# top_g.net
KiCad netlist of a schematic drawn in Altium Designer
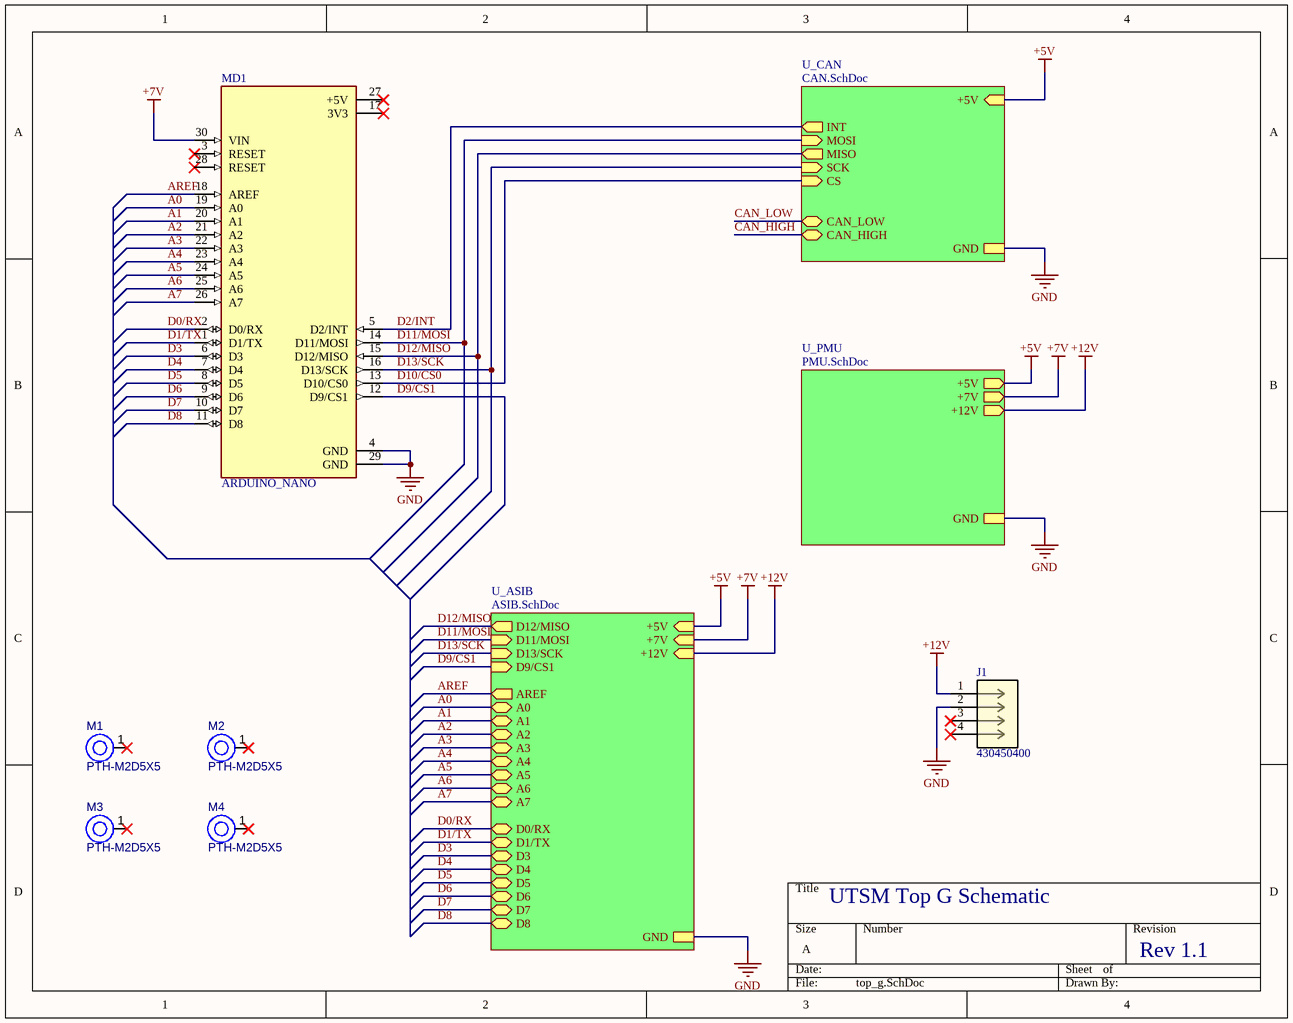
[diagram p0: top_g.SchDoc]

(export (version "E")
  (design (tool "Eeschema 10.0.6"))
  (components
    (comp (ref "J1")
      (value "430450400")
      (footprint "top_g:CON_430450400_MOL")
      (description "+12 from Battery")
      (libsource (lib "top_g") (part "430450400"))
    )
    (comp (ref "M1")
      (value "PTH-M2D5X5")
      (footprint "PTH-M2D5X5")
      (description "M2 PTH (2.5mm), 5mm pad")
      (libsource (lib "top_g") (part "PTH-M2D5X5"))
    )
    (comp (ref "M2")
      (value "PTH-M2D5X5")
      (footprint "PTH-M2D5X5")
      (description "M2 PTH (2.5mm), 5mm pad")
      (libsource (lib "top_g") (part "PTH-M2D5X5"))
    )
    (comp (ref "M3")
      (value "PTH-M2D5X5")
      (footprint "PTH-M2D5X5")
      (description "M2 PTH (2.5mm), 5mm pad")
      (libsource (lib "top_g") (part "PTH-M2D5X5"))
    )
    (comp (ref "M4")
      (value "PTH-M2D5X5")
      (footprint "PTH-M2D5X5")
      (description "M2 PTH (2.5mm), 5mm pad")
      (libsource (lib "top_g") (part "PTH-M2D5X5"))
    )
    (comp (ref "MD1")
      (value "ARDUINO_NANO")
      (footprint "SHIELD_ARDUINO_NANO")
      (description "Small, complete, and breadboard-friendly board based on the ATmega328 (Arduino Nano 3.x)")
      (fields (field (name "MP") "Arduino Nano") (field (name "MF") "Arduino"))
      (libsource (lib "top_g") (part "ARDUINO_NANO"))
    )
  )
  (nets
    (net (code "2") (name "+7V") (class "Default")
      (node (ref "MD1") (pin "30") (pinfunction "VIN_30") (pintype "input"))
    )
    (net (code "3") (name "+12V") (class "Default")
      (node (ref "J1") (pin "1") (pinfunction "1_1") (pintype "passive"))
    )
    (net (code "4") (name "/A0") (class "Default")
      (node (ref "MD1") (pin "19") (pinfunction "A0_19") (pintype "input"))
    )
    (net (code "5") (name "/A1") (class "Default")
      (node (ref "MD1") (pin "20") (pinfunction "A1_20") (pintype "input"))
    )
    (net (code "6") (name "/A2") (class "Default")
      (node (ref "MD1") (pin "21") (pinfunction "A2_21") (pintype "input"))
    )
    (net (code "7") (name "/A3") (class "Default")
      (node (ref "MD1") (pin "22") (pinfunction "A3_22") (pintype "input"))
    )
    (net (code "8") (name "/A4") (class "Default")
      (node (ref "MD1") (pin "23") (pinfunction "A4_23") (pintype "input"))
    )
    (net (code "9") (name "/A5") (class "Default")
      (node (ref "MD1") (pin "24") (pinfunction "A5_24") (pintype "input"))
    )
    (net (code "10") (name "/A6") (class "Default")
      (node (ref "MD1") (pin "25") (pinfunction "A6_25") (pintype "input"))
    )
    (net (code "11") (name "/A7") (class "Default")
      (node (ref "MD1") (pin "26") (pinfunction "A7_26") (pintype "input"))
    )
    (net (code "12") (name "/AREF") (class "Default")
      (node (ref "MD1") (pin "18") (pinfunction "AREF_18") (pintype "input"))
    )
    (net (code "15") (name "/D0{slash}RX") (class "Default")
      (node (ref "MD1") (pin "2") (pinfunction "D0/RX_2") (pintype "bidirectional"))
    )
    (net (code "16") (name "/D1{slash}TX") (class "Default")
      (node (ref "MD1") (pin "1") (pinfunction "D1/TX_1") (pintype "bidirectional"))
    )
    (net (code "17") (name "/D2{slash}INT") (class "Default")
      (node (ref "MD1") (pin "5") (pinfunction "D2/INT_5") (pintype "input"))
    )
    (net (code "18") (name "/D3") (class "Default")
      (node (ref "MD1") (pin "6") (pinfunction "D3_6") (pintype "bidirectional"))
    )
    (net (code "19") (name "/D4") (class "Default")
      (node (ref "MD1") (pin "7") (pinfunction "D4_7") (pintype "bidirectional"))
    )
    (net (code "20") (name "/D5") (class "Default")
      (node (ref "MD1") (pin "8") (pinfunction "D5_8") (pintype "bidirectional"))
    )
    (net (code "21") (name "/D6") (class "Default")
      (node (ref "MD1") (pin "9") (pinfunction "D6_9") (pintype "bidirectional"))
    )
    (net (code "22") (name "/D7") (class "Default")
      (node (ref "MD1") (pin "10") (pinfunction "D7_10") (pintype "bidirectional"))
    )
    (net (code "23") (name "/D8") (class "Default")
      (node (ref "MD1") (pin "11") (pinfunction "D8_11") (pintype "bidirectional"))
    )
    (net (code "24") (name "/D9{slash}CS1") (class "Default")
      (node (ref "MD1") (pin "12") (pinfunction "D9/CS1_12") (pintype "output"))
    )
    (net (code "25") (name "/D10{slash}CS0") (class "Default")
      (node (ref "MD1") (pin "13") (pinfunction "D10/CS0_13") (pintype "output"))
    )
    (net (code "26") (name "/D11{slash}MOSI") (class "Default")
      (node (ref "MD1") (pin "14") (pinfunction "D11/MOSI_14") (pintype "output"))
    )
    (net (code "27") (name "/D12{slash}MISO") (class "Default")
      (node (ref "MD1") (pin "15") (pinfunction "D12/MISO_15") (pintype "input"))
    )
    (net (code "28") (name "/D13{slash}SCK") (class "Default")
      (node (ref "MD1") (pin "16") (pinfunction "D13/SCK_16") (pintype "output"))
    )
    (net (code "29") (name "GND") (class "Default")
      (node (ref "J1") (pin "2") (pinfunction "2_2") (pintype "passive"))
      (node (ref "MD1") (pin "29") (pinfunction "GND_29") (pintype "power_in"))
      (node (ref "MD1") (pin "4") (pinfunction "GND_4") (pintype "power_in"))
    )
    (net (code "30") (name "unconnected-(J1-Pad3)") (class "Default")
      (node (ref "J1") (pin "3") (pinfunction "3_3") (pintype "passive+no_connect"))
    )
    (net (code "31") (name "unconnected-(J1-Pad4)") (class "Default")
      (node (ref "J1") (pin "4") (pinfunction "4_4") (pintype "passive+no_connect"))
    )
    (net (code "32") (name "unconnected-(M1-H1-Pad1)") (class "Default")
      (node (ref "M1") (pin "1") (pinfunction "H1_1") (pintype "passive+no_connect"))
    )
    (net (code "33") (name "unconnected-(M2-H1-Pad1)") (class "Default")
      (node (ref "M2") (pin "1") (pinfunction "H1_1") (pintype "passive+no_connect"))
    )
    (net (code "34") (name "unconnected-(M3-H1-Pad1)") (class "Default")
      (node (ref "M3") (pin "1") (pinfunction "H1_1") (pintype "passive+no_connect"))
    )
    (net (code "35") (name "unconnected-(M4-H1-Pad1)") (class "Default")
      (node (ref "M4") (pin "1") (pinfunction "H1_1") (pintype "passive+no_connect"))
    )
    (net (code "36") (name "unconnected-(MD1-+5V-Pad27)") (class "Default")
      (node (ref "MD1") (pin "27") (pinfunction "+5V_27") (pintype "power_in+no_connect"))
    )
    (net (code "37") (name "unconnected-(MD1-3V3-Pad17)") (class "Default")
      (node (ref "MD1") (pin "17") (pinfunction "3V3_17") (pintype "power_in+no_connect"))
    )
    (net (code "38") (name "unconnected-(MD1-RESET-Pad3)") (class "Default")
      (node (ref "MD1") (pin "3") (pinfunction "RESET_3") (pintype "input+no_connect"))
    )
    (net (code "39") (name "unconnected-(MD1-RESET-Pad28)") (class "Default")
      (node (ref "MD1") (pin "28") (pinfunction "RESET_28") (pintype "input+no_connect"))
    )
  )
)
